# K60FN_LQFP144.net
KiCad netlist of a schematic drawn in Altium Designer
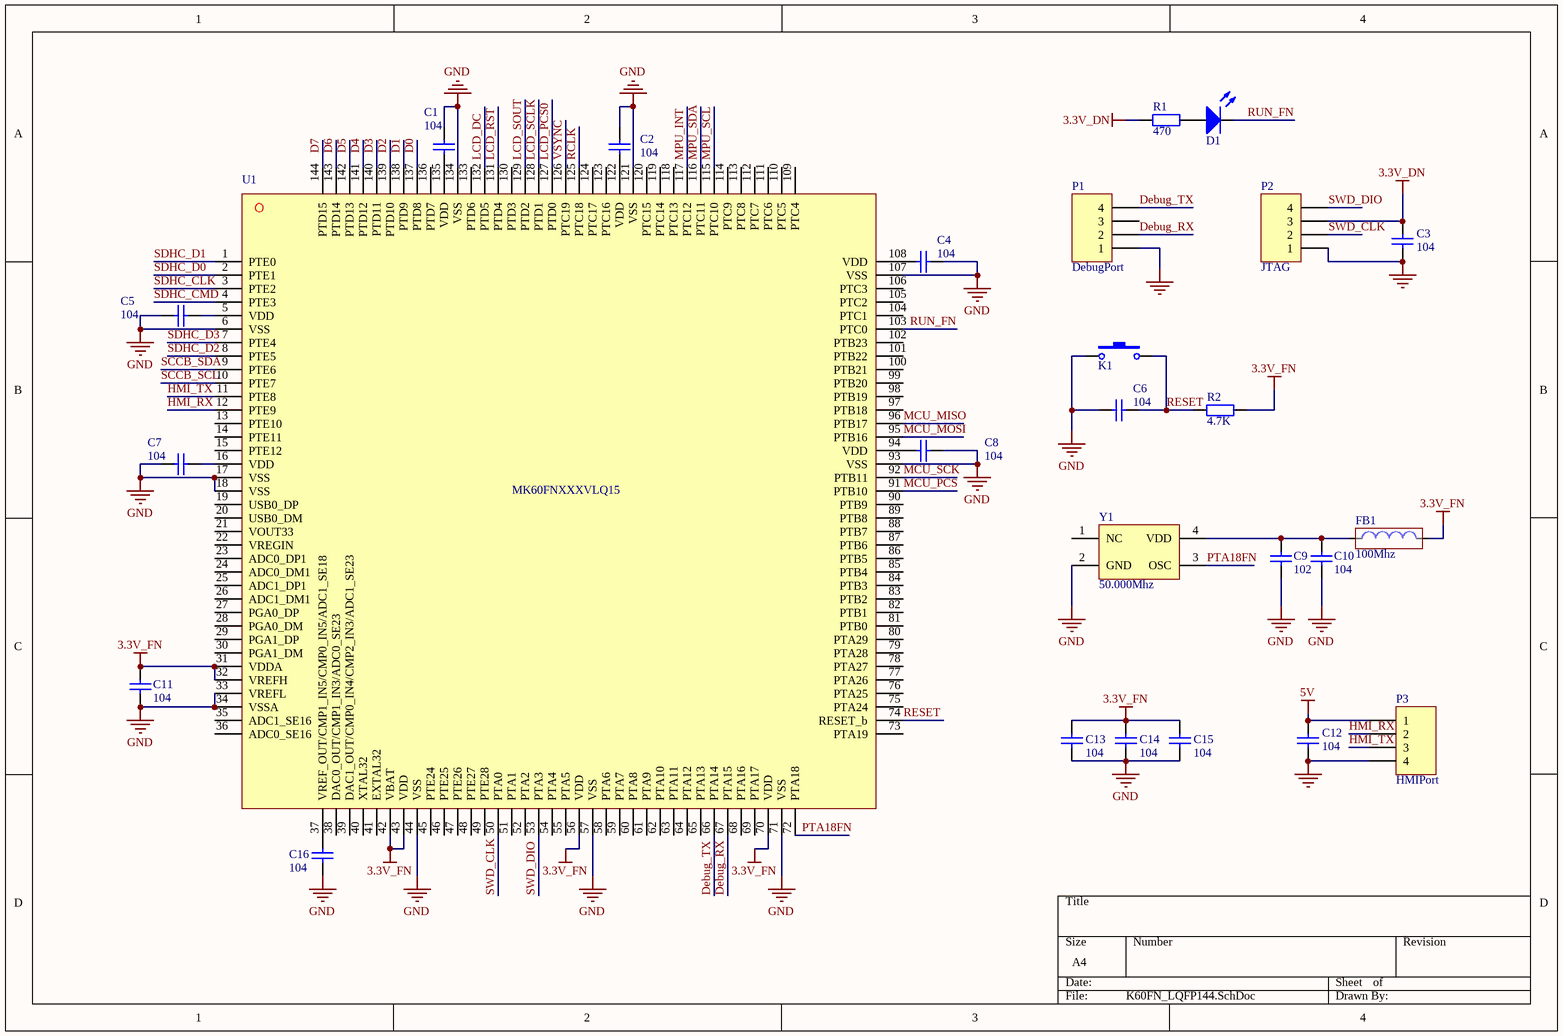
[diagram p0: K60FN_LQFP144.SchDoc]

(export (version "E")
  (design (tool "Eeschema 10.0.6"))
  (components
    (comp (ref "C1") (value "104") (footprint "0805") (libsource (lib "飞思卡尔") (part "Cap")))
    (comp (ref "C2") (value "104") (footprint "0805") (libsource (lib "飞思卡尔") (part "Cap")))
    (comp (ref "C3") (value "104") (footprint "0805") (libsource (lib "飞思卡尔") (part "Cap")))
    (comp (ref "C4") (value "104") (footprint "0805") (libsource (lib "飞思卡尔") (part "Cap")))
    (comp (ref "C5") (value "104") (footprint "0805") (libsource (lib "飞思卡尔") (part "Cap")))
    (comp (ref "C6") (value "104") (footprint "0805") (libsource (lib "飞思卡尔") (part "Cap")))
    (comp (ref "C7") (value "104") (footprint "0805") (libsource (lib "飞思卡尔") (part "Cap")))
    (comp (ref "C8") (value "104") (footprint "0805") (libsource (lib "飞思卡尔") (part "Cap")))
    (comp (ref "C9") (value "102") (footprint "0805") (libsource (lib "飞思卡尔") (part "Cap")))
    (comp (ref "C10") (value "104") (footprint "0805") (libsource (lib "飞思卡尔") (part "Cap")))
    (comp (ref "C11") (value "104") (footprint "0805") (libsource (lib "飞思卡尔") (part "Cap")))
    (comp (ref "C12") (value "104") (footprint "0805") (libsource (lib "飞思卡尔") (part "Cap")))
    (comp (ref "C13") (value "104") (footprint "0805") (libsource (lib "飞思卡尔") (part "Cap")))
    (comp (ref "C14") (value "104") (footprint "0805") (libsource (lib "飞思卡尔") (part "Cap")))
    (comp (ref "C15") (value "104") (footprint "0805") (libsource (lib "飞思卡尔") (part "Cap")))
    (comp (ref "C16") (value "104") (footprint "0805") (libsource (lib "飞思卡尔") (part "Cap")))
    (comp (ref "D1") (value "Led") (footprint "0805") (libsource (lib "飞思卡尔") (part "Led")))
    (comp (ref "FB1") (value "100Mhz") (footprint "0805") (libsource (lib "飞思卡尔") (part "Inductor")))
    (comp (ref "K1") (value "SW-PB") (footprint "2P按键") (libsource (lib "飞思卡尔") (part "SW-PB")))
    (comp (ref "P1")
      (value "DebugPort")
      (footprint "PJ-322")
      (description "Header, 4-Pin")
      (fields (field (name "PUBLISHER") "Altium Limited"))
      (libsource (lib "Miscellaneous Connectors") (part "Header 4"))
    )
    (comp (ref "P2")
      (value "JTAG")
      (footprint "PJ-322")
      (description "Header, 4-Pin")
      (fields (field (name "PUBLISHER") "Altium Limited"))
      (libsource (lib "Miscellaneous Connectors") (part "Header 4"))
    )
    (comp (ref "P3")
      (value "HMIPort")
      (footprint "4P-2.54")
      (description "Header, 4-Pin")
      (fields (field (name "PUBLISHER") "Altium Limited"))
      (libsource (lib "") (part "Header 4_1"))
    )
    (comp (ref "R1") (value "470") (footprint "0805") (libsource (lib "飞思卡尔") (part "Rest")))
    (comp (ref "R2") (value "4.7K") (footprint "0805") (libsource (lib "飞思卡尔") (part "Rest")))
    (comp (ref "U1") (value "MK60FNXXXVLQ15") (footprint "LQFP-144") (libsource (lib "飞思卡尔") (part "K60")))
    (comp (ref "Y1") (value "50.000Mhz") (footprint "XTAL-3225") (libsource (lib "飞思卡尔") (part "有源晶振")))
  )
  (nets
    (net (code "1") (name "/D0") (class "Default")
      (node (ref "U1") (pin "137") (pinfunction "PTD8_137") (pintype "passive"))
    )
    (net (code "2") (name "/D1") (class "Default")
      (node (ref "U1") (pin "138") (pinfunction "PTD9_138") (pintype "passive"))
    )
    (net (code "3") (name "/D2") (class "Default")
      (node (ref "U1") (pin "139") (pinfunction "PTD10_139") (pintype "passive"))
    )
    (net (code "4") (name "/D3") (class "Default")
      (node (ref "U1") (pin "140") (pinfunction "PTD11_140") (pintype "passive"))
    )
    (net (code "5") (name "/D4") (class "Default")
      (node (ref "U1") (pin "141") (pinfunction "PTD12_141") (pintype "passive"))
    )
    (net (code "6") (name "/D5") (class "Default")
      (node (ref "U1") (pin "142") (pinfunction "PTD13_142") (pintype "passive"))
    )
    (net (code "7") (name "/D6") (class "Default")
      (node (ref "U1") (pin "143") (pinfunction "PTD14_143") (pintype "passive"))
    )
    (net (code "8") (name "/D7") (class "Default")
      (node (ref "U1") (pin "144") (pinfunction "PTD15_144") (pintype "passive"))
    )
    (net (code "9") (name "/Debug_RX") (class "Default")
      (node (ref "P1") (pin "2") (pinfunction "2_2") (pintype "passive"))
      (node (ref "U1") (pin "67") (pinfunction "PTA15_67") (pintype "passive"))
    )
    (net (code "10") (name "/Debug_TX") (class "Default")
      (node (ref "P1") (pin "4") (pinfunction "4_4") (pintype "passive"))
      (node (ref "U1") (pin "66") (pinfunction "PTA14_66") (pintype "passive"))
    )
    (net (code "11") (name "/HMI_RX") (class "Default")
      (node (ref "P3") (pin "2") (pinfunction "2_2") (pintype "passive"))
      (node (ref "U1") (pin "12") (pinfunction "PTE9_12") (pintype "passive"))
    )
    (net (code "12") (name "/HMI_TX") (class "Default")
      (node (ref "P3") (pin "3") (pinfunction "3_3") (pintype "passive"))
      (node (ref "U1") (pin "11") (pinfunction "PTE8_11") (pintype "passive"))
    )
    (net (code "13") (name "/LCD_DC") (class "Default")
      (node (ref "U1") (pin "132") (pinfunction "PTD5_132") (pintype "passive"))
    )
    (net (code "14") (name "/LCD_PCS0") (class "Default")
      (node (ref "U1") (pin "127") (pinfunction "PTD0_127") (pintype "passive"))
    )
    (net (code "15") (name "/LCD_RST") (class "Default")
      (node (ref "U1") (pin "131") (pinfunction "PTD4_131") (pintype "passive"))
    )
    (net (code "16") (name "/LCD_SCLK") (class "Default")
      (node (ref "U1") (pin "128") (pinfunction "PTD1_128") (pintype "passive"))
    )
    (net (code "17") (name "/LCD_SOUT") (class "Default")
      (node (ref "U1") (pin "129") (pinfunction "PTD2_129") (pintype "passive"))
    )
    (net (code "18") (name "/MCU_MISO") (class "Default")
      (node (ref "U1") (pin "96") (pinfunction "PTB17_96") (pintype "passive"))
    )
    (net (code "19") (name "/MCU_MOSI") (class "Default")
      (node (ref "U1") (pin "95") (pinfunction "PTB16_95") (pintype "passive"))
    )
    (net (code "20") (name "/MCU_PCS") (class "Default")
      (node (ref "U1") (pin "91") (pinfunction "PTB10_91") (pintype "passive"))
    )
    (net (code "21") (name "/MCU_SCK") (class "Default")
      (node (ref "U1") (pin "92") (pinfunction "PTB11_92") (pintype "passive"))
    )
    (net (code "22") (name "/MPU_INT") (class "Default")
      (node (ref "U1") (pin "117") (pinfunction "PTC12_117") (pintype "passive"))
    )
    (net (code "23") (name "/MPU_SCL") (class "Default")
      (node (ref "U1") (pin "115") (pinfunction "PTC10_115") (pintype "passive"))
    )
    (net (code "24") (name "/MPU_SDA") (class "Default")
      (node (ref "U1") (pin "116") (pinfunction "PTC11_116") (pintype "passive"))
    )
    (net (code "25") (name "/PTA18FN") (class "Default")
      (node (ref "U1") (pin "72") (pinfunction "PTA18_72") (pintype "passive"))
      (node (ref "Y1") (pin "3") (pinfunction "OSC_3") (pintype "passive"))
    )
    (net (code "26") (name "/RCLK") (class "Default")
      (node (ref "U1") (pin "125") (pinfunction "PTC18_125") (pintype "passive"))
    )
    (net (code "27") (name "/RESET") (class "Default")
      (node (ref "C6") (pin "2") (pinfunction "2_2") (pintype "passive"))
      (node (ref "K1") (pin "2") (pinfunction "2_2") (pintype "passive"))
      (node (ref "R2") (pin "1") (pinfunction "1_1") (pintype "passive"))
      (node (ref "U1") (pin "74") (pinfunction "RESET_b_74") (pintype "passive"))
    )
    (net (code "28") (name "/RUN_FN") (class "Default")
      (node (ref "D1") (pin "2") (pinfunction "2_2") (pintype "passive"))
      (node (ref "U1") (pin "103") (pinfunction "PTC0_103") (pintype "passive"))
    )
    (net (code "29") (name "/SCCB_SCL") (class "Default")
      (node (ref "U1") (pin "10") (pinfunction "PTE7_10") (pintype "passive"))
    )
    (net (code "30") (name "/SCCB_SDA") (class "Default")
      (node (ref "U1") (pin "9") (pinfunction "PTE6_9") (pintype "passive"))
    )
    (net (code "31") (name "/SDHC_CLK") (class "Default")
      (node (ref "U1") (pin "3") (pinfunction "PTE2_3") (pintype "passive"))
    )
    (net (code "32") (name "/SDHC_CMD") (class "Default")
      (node (ref "U1") (pin "4") (pinfunction "PTE3_4") (pintype "passive"))
    )
    (net (code "33") (name "/SDHC_D0") (class "Default")
      (node (ref "U1") (pin "2") (pinfunction "PTE1_2") (pintype "passive"))
    )
    (net (code "34") (name "/SDHC_D1") (class "Default")
      (node (ref "U1") (pin "1") (pinfunction "PTE0_1") (pintype "passive"))
    )
    (net (code "35") (name "/SDHC_D2") (class "Default")
      (node (ref "U1") (pin "8") (pinfunction "PTE5_8") (pintype "passive"))
    )
    (net (code "36") (name "/SDHC_D3") (class "Default")
      (node (ref "U1") (pin "7") (pinfunction "PTE4_7") (pintype "passive"))
    )
    (net (code "37") (name "/SWD_CLK") (class "Default")
      (node (ref "P2") (pin "2") (pinfunction "2_2") (pintype "passive"))
      (node (ref "U1") (pin "50") (pinfunction "PTA0_50") (pintype "passive"))
    )
    (net (code "38") (name "/SWD_DIO") (class "Default")
      (node (ref "P2") (pin "4") (pinfunction "4_4") (pintype "passive"))
      (node (ref "U1") (pin "53") (pinfunction "PTA3_53") (pintype "passive"))
    )
    (net (code "39") (name "/VSYNC") (class "Default")
      (node (ref "U1") (pin "126") (pinfunction "PTC19_126") (pintype "passive"))
    )
    (net (code "40") (name "3.3V_DN") (class "Default")
      (node (ref "C3") (pin "1") (pinfunction "1_1") (pintype "passive"))
      (node (ref "P2") (pin "3") (pinfunction "3_3") (pintype "passive"))
      (node (ref "R1") (pin "1") (pinfunction "1_1") (pintype "passive"))
    )
    (net (code "41") (name "3.3V_FN") (class "Default")
      (node (ref "C11") (pin "2") (pinfunction "2_2") (pintype "passive"))
      (node (ref "C13") (pin "2") (pinfunction "2_2") (pintype "passive"))
      (node (ref "C14") (pin "2") (pinfunction "2_2") (pintype "passive"))
      (node (ref "C15") (pin "2") (pinfunction "2_2") (pintype "passive"))
      (node (ref "FB1") (pin "2") (pinfunction "2_2") (pintype "passive"))
      (node (ref "R2") (pin "2") (pinfunction "2_2") (pintype "passive"))
      (node (ref "U1") (pin "31") (pinfunction "VDDA_31") (pintype "passive"))
      (node (ref "U1") (pin "32") (pinfunction "VREFH_32") (pintype "passive"))
      (node (ref "U1") (pin "42") (pinfunction "VBAT_42") (pintype "passive"))
      (node (ref "U1") (pin "43") (pinfunction "VDD_43") (pintype "passive"))
      (node (ref "U1") (pin "56") (pinfunction "VDD_56") (pintype "passive"))
      (node (ref "U1") (pin "70") (pinfunction "VDD_70") (pintype "passive"))
    )
    (net (code "42") (name "5V") (class "Default")
      (node (ref "C12") (pin "2") (pinfunction "2_2") (pintype "passive"))
      (node (ref "P3") (pin "1") (pinfunction "1_1") (pintype "passive"))
    )
    (net (code "43") (name "GND") (class "Default")
      (node (ref "C1") (pin "2") (pinfunction "2_2") (pintype "passive"))
      (node (ref "C10") (pin "1") (pinfunction "1_1") (pintype "passive"))
      (node (ref "C11") (pin "1") (pinfunction "1_1") (pintype "passive"))
      (node (ref "C12") (pin "1") (pinfunction "1_1") (pintype "passive"))
      (node (ref "C13") (pin "1") (pinfunction "1_1") (pintype "passive"))
      (node (ref "C14") (pin "1") (pinfunction "1_1") (pintype "passive"))
      (node (ref "C15") (pin "1") (pinfunction "1_1") (pintype "passive"))
      (node (ref "C16") (pin "1") (pinfunction "1_1") (pintype "passive"))
      (node (ref "C2") (pin "2") (pinfunction "2_2") (pintype "passive"))
      (node (ref "C3") (pin "2") (pinfunction "2_2") (pintype "passive"))
      (node (ref "C4") (pin "1") (pinfunction "1_1") (pintype "passive"))
      (node (ref "C5") (pin "1") (pinfunction "1_1") (pintype "passive"))
      (node (ref "C6") (pin "1") (pinfunction "1_1") (pintype "passive"))
      (node (ref "C7") (pin "1") (pinfunction "1_1") (pintype "passive"))
      (node (ref "C8") (pin "1") (pinfunction "1_1") (pintype "passive"))
      (node (ref "C9") (pin "1") (pinfunction "1_1") (pintype "passive"))
      (node (ref "K1") (pin "1") (pinfunction "1_1") (pintype "passive"))
      (node (ref "P1") (pin "1") (pinfunction "1_1") (pintype "passive"))
      (node (ref "P2") (pin "1") (pinfunction "1_1") (pintype "passive"))
      (node (ref "P3") (pin "4") (pinfunction "4_4") (pintype "passive"))
      (node (ref "U1") (pin "107") (pinfunction "VSS_107") (pintype "passive"))
      (node (ref "U1") (pin "121") (pinfunction "VSS_121") (pintype "passive"))
      (node (ref "U1") (pin "134") (pinfunction "VSS_134") (pintype "passive"))
      (node (ref "U1") (pin "17") (pinfunction "VSS_17") (pintype "passive"))
      (node (ref "U1") (pin "18") (pinfunction "VSS_18") (pintype "passive"))
      (node (ref "U1") (pin "33") (pinfunction "VREFL_33") (pintype "passive"))
      (node (ref "U1") (pin "34") (pinfunction "VSSA_34") (pintype "passive"))
      (node (ref "U1") (pin "44") (pinfunction "VSS_44") (pintype "passive"))
      (node (ref "U1") (pin "57") (pinfunction "VSS_57") (pintype "passive"))
      (node (ref "U1") (pin "6") (pinfunction "VSS_6") (pintype "passive"))
      (node (ref "U1") (pin "71") (pinfunction "VSS_71") (pintype "passive"))
      (node (ref "U1") (pin "93") (pinfunction "VSS_93") (pintype "passive"))
      (node (ref "Y1") (pin "2") (pinfunction "GND_2") (pintype "passive"))
    )
    (net (code "44") (name "Net-(C1-Pad1)") (class "Default")
      (node (ref "C1") (pin "1") (pinfunction "1_1") (pintype "passive"))
      (node (ref "U1") (pin "135") (pinfunction "VDD_135") (pintype "passive"))
    )
    (net (code "45") (name "Net-(C2-Pad1)") (class "Default")
      (node (ref "C2") (pin "1") (pinfunction "1_1") (pintype "passive"))
      (node (ref "U1") (pin "122") (pinfunction "VDD_122") (pintype "passive"))
    )
    (net (code "46") (name "Net-(C4-Pad2)") (class "Default")
      (node (ref "C4") (pin "2") (pinfunction "2_2") (pintype "passive"))
      (node (ref "U1") (pin "108") (pinfunction "VDD_108") (pintype "passive"))
    )
    (net (code "47") (name "Net-(C5-Pad2)") (class "Default")
      (node (ref "C5") (pin "2") (pinfunction "2_2") (pintype "passive"))
      (node (ref "U1") (pin "5") (pinfunction "VDD_5") (pintype "passive"))
    )
    (net (code "48") (name "Net-(C7-Pad2)") (class "Default")
      (node (ref "C7") (pin "2") (pinfunction "2_2") (pintype "passive"))
      (node (ref "U1") (pin "16") (pinfunction "VDD_16") (pintype "passive"))
    )
    (net (code "49") (name "Net-(C8-Pad2)") (class "Default")
      (node (ref "C8") (pin "2") (pinfunction "2_2") (pintype "passive"))
      (node (ref "U1") (pin "94") (pinfunction "VDD_94") (pintype "passive"))
    )
    (net (code "50") (name "Net-(D1-Pad1)") (class "Default")
      (node (ref "D1") (pin "1") (pinfunction "1_1") (pintype "passive"))
      (node (ref "R1") (pin "2") (pinfunction "2_2") (pintype "passive"))
    )
    (net (code "51") (name "Net-(U1-VREF_OUT{slash}CMP1_IN5{slash}CMP0_IN5{slash}ADC1_SE18)") (class "Default")
      (node (ref "C16") (pin "2") (pinfunction "2_2") (pintype "passive"))
      (node (ref "U1") (pin "37") (pinfunction "VREF_OUT/CMP1_IN5/CMP0_IN5/ADC1_SE18_37") (pintype "passive"))
    )
    (net (code "52") (name "Net-(Y1-VDD)") (class "Default")
      (node (ref "C10") (pin "2") (pinfunction "2_2") (pintype "passive"))
      (node (ref "C9") (pin "2") (pinfunction "2_2") (pintype "passive"))
      (node (ref "FB1") (pin "1") (pinfunction "1_1") (pintype "passive"))
      (node (ref "Y1") (pin "4") (pinfunction "VDD_4") (pintype "passive"))
    )
    (net (code "53") (name "unconnected-(P1-Pad3)") (class "Default")
      (node (ref "P1") (pin "3") (pinfunction "3_3") (pintype "passive"))
    )
    (net (code "54") (name "unconnected-(U1-ADC0_DM1-Pad24)") (class "Default")
      (node (ref "U1") (pin "24") (pinfunction "ADC0_DM1_24") (pintype "passive"))
    )
    (net (code "55") (name "unconnected-(U1-ADC0_DP1-Pad23)") (class "Default")
      (node (ref "U1") (pin "23") (pinfunction "ADC0_DP1_23") (pintype "passive"))
    )
    (net (code "56") (name "unconnected-(U1-ADC0_SE16-Pad36)") (class "Default")
      (node (ref "U1") (pin "36") (pinfunction "ADC0_SE16_36") (pintype "passive"))
    )
    (net (code "57") (name "unconnected-(U1-ADC1_DM1-Pad26)") (class "Default")
      (node (ref "U1") (pin "26") (pinfunction "ADC1_DM1_26") (pintype "passive"))
    )
    (net (code "58") (name "unconnected-(U1-ADC1_DP1-Pad25)") (class "Default")
      (node (ref "U1") (pin "25") (pinfunction "ADC1_DP1_25") (pintype "passive"))
    )
    (net (code "59") (name "unconnected-(U1-ADC1_SE16-Pad35)") (class "Default")
      (node (ref "U1") (pin "35") (pinfunction "ADC1_SE16_35") (pintype "passive"))
    )
    (net (code "60") (name "unconnected-(U1-DAC0_OUT{slash}CMP1_IN3{slash}ADC0_SE23-Pad38)") (class "Default")
      (node (ref "U1") (pin "38") (pinfunction "DAC0_OUT/CMP1_IN3/ADC0_SE23_38") (pintype "passive"))
    )
    (net (code "61") (name "unconnected-(U1-DAC1_OUT{slash}CMP0_IN4{slash}CMP2_IN3{slash}ADC1_SE23-Pad39)") (class "Default")
      (node (ref "U1") (pin "39") (pinfunction "DAC1_OUT/CMP0_IN4/CMP2_IN3/ADC1_SE23_39") (pintype "passive"))
    )
    (net (code "62") (name "unconnected-(U1-EXTAL32-Pad41)") (class "Default")
      (node (ref "U1") (pin "41") (pinfunction "EXTAL32_41") (pintype "passive"))
    )
    (net (code "63") (name "unconnected-(U1-PGA0_DM-Pad28)") (class "Default")
      (node (ref "U1") (pin "28") (pinfunction "PGA0_DM_28") (pintype "passive"))
    )
    (net (code "64") (name "unconnected-(U1-PGA0_DP-Pad27)") (class "Default")
      (node (ref "U1") (pin "27") (pinfunction "PGA0_DP_27") (pintype "passive"))
    )
    (net (code "65") (name "unconnected-(U1-PGA1_DM-Pad30)") (class "Default")
      (node (ref "U1") (pin "30") (pinfunction "PGA1_DM_30") (pintype "passive"))
    )
    (net (code "66") (name "unconnected-(U1-PGA1_DP-Pad29)") (class "Default")
      (node (ref "U1") (pin "29") (pinfunction "PGA1_DP_29") (pintype "passive"))
    )
    (net (code "67") (name "unconnected-(U1-PTA1-Pad51)") (class "Default")
      (node (ref "U1") (pin "51") (pinfunction "PTA1_51") (pintype "passive"))
    )
    (net (code "68") (name "unconnected-(U1-PTA2-Pad52)") (class "Default")
      (node (ref "U1") (pin "52") (pinfunction "PTA2_52") (pintype "passive"))
    )
    (net (code "69") (name "unconnected-(U1-PTA4-Pad54)") (class "Default")
      (node (ref "U1") (pin "54") (pinfunction "PTA4_54") (pintype "passive"))
    )
    (net (code "70") (name "unconnected-(U1-PTA5-Pad55)") (class "Default")
      (node (ref "U1") (pin "55") (pinfunction "PTA5_55") (pintype "passive"))
    )
    (net (code "71") (name "unconnected-(U1-PTA6-Pad58)") (class "Default")
      (node (ref "U1") (pin "58") (pinfunction "PTA6_58") (pintype "passive"))
    )
    (net (code "72") (name "unconnected-(U1-PTA7-Pad59)") (class "Default")
      (node (ref "U1") (pin "59") (pinfunction "PTA7_59") (pintype "passive"))
    )
    (net (code "73") (name "unconnected-(U1-PTA8-Pad60)") (class "Default")
      (node (ref "U1") (pin "60") (pinfunction "PTA8_60") (pintype "passive"))
    )
    (net (code "74") (name "unconnected-(U1-PTA9-Pad61)") (class "Default")
      (node (ref "U1") (pin "61") (pinfunction "PTA9_61") (pintype "passive"))
    )
    (net (code "75") (name "unconnected-(U1-PTA10-Pad62)") (class "Default")
      (node (ref "U1") (pin "62") (pinfunction "PTA10_62") (pintype "passive"))
    )
    (net (code "76") (name "unconnected-(U1-PTA11-Pad63)") (class "Default")
      (node (ref "U1") (pin "63") (pinfunction "PTA11_63") (pintype "passive"))
    )
    (net (code "77") (name "unconnected-(U1-PTA12-Pad64)") (class "Default")
      (node (ref "U1") (pin "64") (pinfunction "PTA12_64") (pintype "passive"))
    )
    (net (code "78") (name "unconnected-(U1-PTA13-Pad65)") (class "Default")
      (node (ref "U1") (pin "65") (pinfunction "PTA13_65") (pintype "passive"))
    )
    (net (code "79") (name "unconnected-(U1-PTA16-Pad68)") (class "Default")
      (node (ref "U1") (pin "68") (pinfunction "PTA16_68") (pintype "passive"))
    )
    (net (code "80") (name "unconnected-(U1-PTA17-Pad69)") (class "Default")
      (node (ref "U1") (pin "69") (pinfunction "PTA17_69") (pintype "passive"))
    )
    (net (code "81") (name "unconnected-(U1-PTA19-Pad73)") (class "Default")
      (node (ref "U1") (pin "73") (pinfunction "PTA19_73") (pintype "passive"))
    )
    (net (code "82") (name "unconnected-(U1-PTA24-Pad75)") (class "Default")
      (node (ref "U1") (pin "75") (pinfunction "PTA24_75") (pintype "passive"))
    )
    (net (code "83") (name "unconnected-(U1-PTA25-Pad76)") (class "Default")
      (node (ref "U1") (pin "76") (pinfunction "PTA25_76") (pintype "passive"))
    )
    (net (code "84") (name "unconnected-(U1-PTA26-Pad77)") (class "Default")
      (node (ref "U1") (pin "77") (pinfunction "PTA26_77") (pintype "passive"))
    )
    (net (code "85") (name "unconnected-(U1-PTA27-Pad78)") (class "Default")
      (node (ref "U1") (pin "78") (pinfunction "PTA27_78") (pintype "passive"))
    )
    (net (code "86") (name "unconnected-(U1-PTA28-Pad79)") (class "Default")
      (node (ref "U1") (pin "79") (pinfunction "PTA28_79") (pintype "passive"))
    )
    (net (code "87") (name "unconnected-(U1-PTA29-Pad80)") (class "Default")
      (node (ref "U1") (pin "80") (pinfunction "PTA29_80") (pintype "passive"))
    )
    (net (code "88") (name "unconnected-(U1-PTB0-Pad81)") (class "Default")
      (node (ref "U1") (pin "81") (pinfunction "PTB0_81") (pintype "passive"))
    )
    (net (code "89") (name "unconnected-(U1-PTB1-Pad82)") (class "Default")
      (node (ref "U1") (pin "82") (pinfunction "PTB1_82") (pintype "passive"))
    )
    (net (code "90") (name "unconnected-(U1-PTB2-Pad83)") (class "Default")
      (node (ref "U1") (pin "83") (pinfunction "PTB2_83") (pintype "passive"))
    )
    (net (code "91") (name "unconnected-(U1-PTB3-Pad84)") (class "Default")
      (node (ref "U1") (pin "84") (pinfunction "PTB3_84") (pintype "passive"))
    )
    (net (code "92") (name "unconnected-(U1-PTB4-Pad85)") (class "Default")
      (node (ref "U1") (pin "85") (pinfunction "PTB4_85") (pintype "passive"))
    )
    (net (code "93") (name "unconnected-(U1-PTB5-Pad86)") (class "Default")
      (node (ref "U1") (pin "86") (pinfunction "PTB5_86") (pintype "passive"))
    )
    (net (code "94") (name "unconnected-(U1-PTB6-Pad87)") (class "Default")
      (node (ref "U1") (pin "87") (pinfunction "PTB6_87") (pintype "passive"))
    )
    (net (code "95") (name "unconnected-(U1-PTB7-Pad88)") (class "Default")
      (node (ref "U1") (pin "88") (pinfunction "PTB7_88") (pintype "passive"))
    )
    (net (code "96") (name "unconnected-(U1-PTB8-Pad89)") (class "Default")
      (node (ref "U1") (pin "89") (pinfunction "PTB8_89") (pintype "passive"))
    )
    (net (code "97") (name "unconnected-(U1-PTB9-Pad90)") (class "Default")
      (node (ref "U1") (pin "90") (pinfunction "PTB9_90") (pintype "passive"))
    )
    (net (code "98") (name "unconnected-(U1-PTB18-Pad97)") (class "Default")
      (node (ref "U1") (pin "97") (pinfunction "PTB18_97") (pintype "passive"))
    )
    (net (code "99") (name "unconnected-(U1-PTB19-Pad98)") (class "Default")
      (node (ref "U1") (pin "98") (pinfunction "PTB19_98") (pintype "passive"))
    )
    (net (code "100") (name "unconnected-(U1-PTB20-Pad99)") (class "Default")
      (node (ref "U1") (pin "99") (pinfunction "PTB20_99") (pintype "passive"))
    )
    (net (code "101") (name "unconnected-(U1-PTB21-Pad100)") (class "Default")
      (node (ref "U1") (pin "100") (pinfunction "PTB21_100") (pintype "passive"))
    )
    (net (code "102") (name "unconnected-(U1-PTB22-Pad101)") (class "Default")
      (node (ref "U1") (pin "101") (pinfunction "PTB22_101") (pintype "passive"))
    )
    (net (code "103") (name "unconnected-(U1-PTB23-Pad102)") (class "Default")
      (node (ref "U1") (pin "102") (pinfunction "PTB23_102") (pintype "passive"))
    )
    (net (code "104") (name "unconnected-(U1-PTC1-Pad104)") (class "Default")
      (node (ref "U1") (pin "104") (pinfunction "PTC1_104") (pintype "passive"))
    )
    (net (code "105") (name "unconnected-(U1-PTC2-Pad105)") (class "Default")
      (node (ref "U1") (pin "105") (pinfunction "PTC2_105") (pintype "passive"))
    )
    (net (code "106") (name "unconnected-(U1-PTC3-Pad106)") (class "Default")
      (node (ref "U1") (pin "106") (pinfunction "PTC3_106") (pintype "passive"))
    )
    (net (code "107") (name "unconnected-(U1-PTC4-Pad109)") (class "Default")
      (node (ref "U1") (pin "109") (pinfunction "PTC4_109") (pintype "passive"))
    )
    (net (code "108") (name "unconnected-(U1-PTC5-Pad110)") (class "Default")
      (node (ref "U1") (pin "110") (pinfunction "PTC5_110") (pintype "passive"))
    )
    (net (code "109") (name "unconnected-(U1-PTC6-Pad111)") (class "Default")
      (node (ref "U1") (pin "111") (pinfunction "PTC6_111") (pintype "passive"))
    )
    (net (code "110") (name "unconnected-(U1-PTC7-Pad112)") (class "Default")
      (node (ref "U1") (pin "112") (pinfunction "PTC7_112") (pintype "passive"))
    )
    (net (code "111") (name "unconnected-(U1-PTC8-Pad113)") (class "Default")
      (node (ref "U1") (pin "113") (pinfunction "PTC8_113") (pintype "passive"))
    )
    (net (code "112") (name "unconnected-(U1-PTC9-Pad114)") (class "Default")
      (node (ref "U1") (pin "114") (pinfunction "PTC9_114") (pintype "passive"))
    )
    (net (code "113") (name "unconnected-(U1-PTC13-Pad118)") (class "Default")
      (node (ref "U1") (pin "118") (pinfunction "PTC13_118") (pintype "passive"))
    )
    (net (code "114") (name "unconnected-(U1-PTC14-Pad119)") (class "Default")
      (node (ref "U1") (pin "119") (pinfunction "PTC14_119") (pintype "passive"))
    )
    (net (code "115") (name "unconnected-(U1-PTC15-Pad120)") (class "Default")
      (node (ref "U1") (pin "120") (pinfunction "PTC15_120") (pintype "passive"))
    )
    (net (code "116") (name "unconnected-(U1-PTC16-Pad123)") (class "Default")
      (node (ref "U1") (pin "123") (pinfunction "PTC16_123") (pintype "passive"))
    )
    (net (code "117") (name "unconnected-(U1-PTC17-Pad124)") (class "Default")
      (node (ref "U1") (pin "124") (pinfunction "PTC17_124") (pintype "passive"))
    )
    (net (code "118") (name "unconnected-(U1-PTD3-Pad130)") (class "Default")
      (node (ref "U1") (pin "130") (pinfunction "PTD3_130") (pintype "passive"))
    )
    (net (code "119") (name "unconnected-(U1-PTD6-Pad133)") (class "Default")
      (node (ref "U1") (pin "133") (pinfunction "PTD6_133") (pintype "passive"))
    )
    (net (code "120") (name "unconnected-(U1-PTD7-Pad136)") (class "Default")
      (node (ref "U1") (pin "136") (pinfunction "PTD7_136") (pintype "passive"))
    )
    (net (code "121") (name "unconnected-(U1-PTE10-Pad13)") (class "Default")
      (node (ref "U1") (pin "13") (pinfunction "PTE10_13") (pintype "passive"))
    )
    (net (code "122") (name "unconnected-(U1-PTE11-Pad14)") (class "Default")
      (node (ref "U1") (pin "14") (pinfunction "PTE11_14") (pintype "passive"))
    )
    (net (code "123") (name "unconnected-(U1-PTE12-Pad15)") (class "Default")
      (node (ref "U1") (pin "15") (pinfunction "PTE12_15") (pintype "passive"))
    )
    (net (code "124") (name "unconnected-(U1-PTE24-Pad45)") (class "Default")
      (node (ref "U1") (pin "45") (pinfunction "PTE24_45") (pintype "passive"))
    )
    (net (code "125") (name "unconnected-(U1-PTE25-Pad46)") (class "Default")
      (node (ref "U1") (pin "46") (pinfunction "PTE25_46") (pintype "passive"))
    )
    (net (code "126") (name "unconnected-(U1-PTE26-Pad47)") (class "Default")
      (node (ref "U1") (pin "47") (pinfunction "PTE26_47") (pintype "passive"))
    )
    (net (code "127") (name "unconnected-(U1-PTE27-Pad48)") (class "Default")
      (node (ref "U1") (pin "48") (pinfunction "PTE27_48") (pintype "passive"))
    )
    (net (code "128") (name "unconnected-(U1-PTE28-Pad49)") (class "Default")
      (node (ref "U1") (pin "49") (pinfunction "PTE28_49") (pintype "passive"))
    )
    (net (code "129") (name "unconnected-(U1-USB0_DM-Pad20)") (class "Default")
      (node (ref "U1") (pin "20") (pinfunction "USB0_DM_20") (pintype "passive"))
    )
    (net (code "130") (name "unconnected-(U1-USB0_DP-Pad19)") (class "Default")
      (node (ref "U1") (pin "19") (pinfunction "USB0_DP_19") (pintype "passive"))
    )
    (net (code "131") (name "unconnected-(U1-VOUT33-Pad21)") (class "Default")
      (node (ref "U1") (pin "21") (pinfunction "VOUT33_21") (pintype "passive"))
    )
    (net (code "132") (name "unconnected-(U1-VREGIN-Pad22)") (class "Default")
      (node (ref "U1") (pin "22") (pinfunction "VREGIN_22") (pintype "passive"))
    )
    (net (code "133") (name "unconnected-(U1-XTAL32-Pad40)") (class "Default")
      (node (ref "U1") (pin "40") (pinfunction "XTAL32_40") (pintype "passive"))
    )
    (net (code "134") (name "unconnected-(Y1-NC-Pad1)") (class "Default")
      (node (ref "Y1") (pin "1") (pinfunction "NC_1") (pintype "passive"))
    )
  )
)
